# FMC_ADC_top.net
KiCad netlist of a schematic drawn in Altium Designer
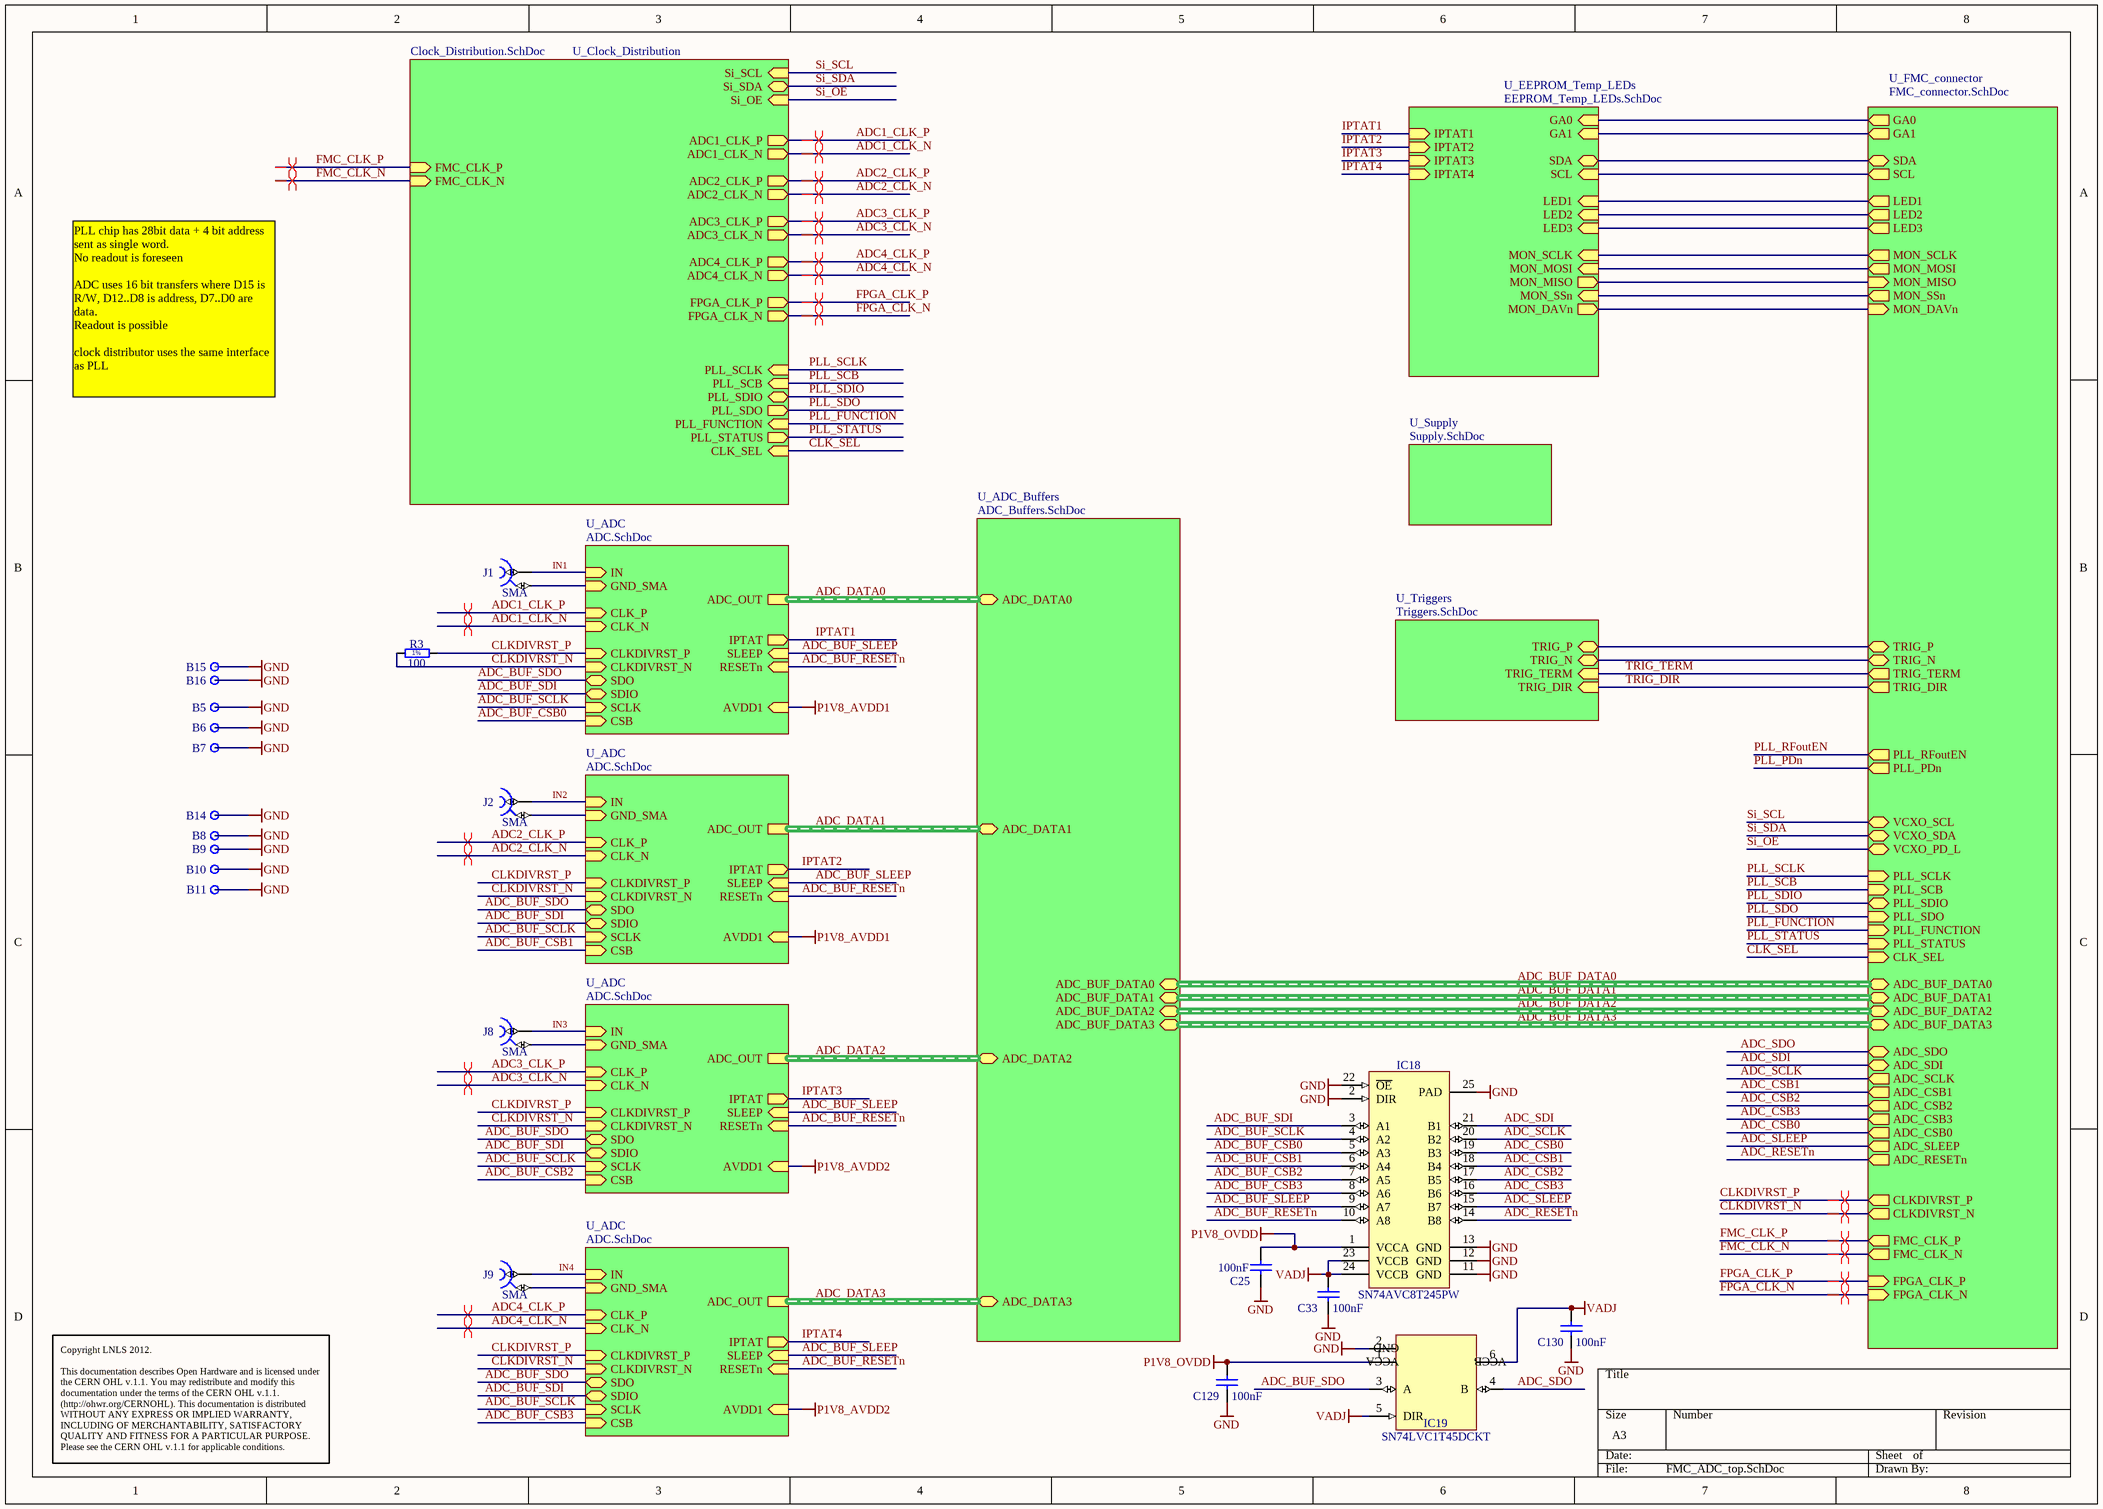
[diagram p0: FMC_ADC_top.SchDoc]

(export (version "E")
  (design (tool "Eeschema 10.0.6"))
  (components
    (comp (ref "B5")
      (value "Plated Hole")
      (footprint "MTG240_400_M")
      (description "Single Terminal Socket")
      (fields (field (name "PART NUMBER") "PLATED_HOLE2.4_PAD4.0_M") (field (name "AUTHOR") "LNLS DIG FCS"))
      (libsource (lib "Eletro-mechanical") (part "Single Terminal Socket"))
    )
    (comp (ref "B6")
      (value "Plated Hole")
      (footprint "MTG240_400_M")
      (description "Single Terminal Socket")
      (fields (field (name "PART NUMBER") "PLATED_HOLE2.4_PAD4.0_M") (field (name "AUTHOR") "LNLS DIG FCS"))
      (libsource (lib "Eletro-mechanical") (part "Single Terminal Socket"))
    )
    (comp (ref "B7")
      (value "Plated Hole")
      (footprint "MTG240_400_M")
      (description "Single Terminal Socket")
      (fields (field (name "PART NUMBER") "PLATED_HOLE2.4_PAD4.0_M") (field (name "AUTHOR") "LNLS DIG FCS"))
      (libsource (lib "Eletro-mechanical") (part "Single Terminal Socket"))
    )
    (comp (ref "B8")
      (value "Plated Hole")
      (footprint "MTG240_400_M")
      (description "Single Terminal Socket")
      (fields (field (name "PART NUMBER") "PLATED_HOLE2.4_PAD4.0_M") (field (name "AUTHOR") "LNLS DIG FCS"))
      (libsource (lib "Eletro-mechanical") (part "Single Terminal Socket"))
    )
    (comp (ref "B9")
      (value "Plated Hole")
      (footprint "MTG240_400_M")
      (description "Single Terminal Socket")
      (fields (field (name "PART NUMBER") "PLATED_HOLE2.4_PAD4.0_M") (field (name "AUTHOR") "LNLS DIG FCS"))
      (libsource (lib "Eletro-mechanical") (part "Single Terminal Socket"))
    )
    (comp (ref "B10")
      (value "Plated Hole")
      (footprint "MTG240_400_M")
      (description "Single Terminal Socket")
      (fields (field (name "PART NUMBER") "PLATED_HOLE2.4_PAD4.0_M") (field (name "AUTHOR") "LNLS DIG FCS"))
      (libsource (lib "Eletro-mechanical") (part "Single Terminal Socket"))
    )
    (comp (ref "B11")
      (value "Plated Hole")
      (footprint "MTG240_400_M")
      (description "Single Terminal Socket")
      (fields (field (name "PART NUMBER") "PLATED_HOLE2.4_PAD4.0_M") (field (name "AUTHOR") "LNLS DIG FCS"))
      (libsource (lib "Eletro-mechanical") (part "Single Terminal Socket"))
    )
    (comp (ref "B14")
      (value "Plated Hole")
      (footprint "MTG240_400_M")
      (description "Single Terminal Socket")
      (fields (field (name "PART NUMBER") "PLATED_HOLE2.4_PAD4.0_M") (field (name "AUTHOR") "LNLS DIG FCS"))
      (libsource (lib "Eletro-mechanical") (part "Single Terminal Socket"))
    )
    (comp (ref "B15")
      (value "Plated Hole")
      (footprint "MTG240_400_M")
      (description "Single Terminal Socket")
      (fields (field (name "PART NUMBER") "PLATED_HOLE2.4_PAD4.0_M") (field (name "AUTHOR") "LNLS DIG FCS"))
      (libsource (lib "Eletro-mechanical") (part "Single Terminal Socket"))
    )
    (comp (ref "B16")
      (value "Plated Hole")
      (footprint "MTG240_400_M")
      (description "Single Terminal Socket")
      (fields (field (name "PART NUMBER") "PLATED_HOLE2.4_PAD4.0_M") (field (name "AUTHOR") "LNLS DIG FCS"))
      (libsource (lib "Eletro-mechanical") (part "Single Terminal Socket"))
    )
    (comp (ref "C25")
      (value "100nF")
      (footprint "CAPC0603X33N")
      (description "Non-polarised capacitor")
      (fields
        (field (name "PART NUMBER") "CC0201_100NF_6.3V_10%_X5R")
        (field (name "VOLTAGE") "6.3V")
        (field (name "AUTHOR") "CERN DEM JLC")
      )
      (libsource (lib "Capacitors") (part "Capacitor - non polarized"))
    )
    (comp (ref "C33")
      (value "100nF")
      (footprint "CAPC0603X33N")
      (description "Non-polarised capacitor")
      (fields
        (field (name "PART NUMBER") "CC0201_100NF_6.3V_10%_X5R")
        (field (name "VOLTAGE") "6.3V")
        (field (name "AUTHOR") "CERN DEM JLC")
      )
      (libsource (lib "Capacitors") (part "Capacitor - non polarized"))
    )
    (comp (ref "C129")
      (value "100nF")
      (footprint "CAPC0603X33N")
      (description "Non-polarised capacitor")
      (fields
        (field (name "PART NUMBER") "CC0201_100NF_6.3V_10%_X5R")
        (field (name "VOLTAGE") "6.3V")
        (field (name "AUTHOR") "CERN DEM JLC")
      )
      (libsource (lib "Capacitors") (part "Capacitor - non polarized"))
    )
    (comp (ref "C130")
      (value "100nF")
      (footprint "CAPC0603X33N")
      (description "Non-polarised capacitor")
      (fields
        (field (name "PART NUMBER") "CC0201_100NF_6.3V_10%_X5R")
        (field (name "VOLTAGE") "6.3V")
        (field (name "AUTHOR") "CERN DEM JLC")
      )
      (libsource (lib "Capacitors") (part "Capacitor - non polarized"))
    )
    (comp (ref "IC18")
      (value "SN74AVC8T245PW")
      (footprint "SOP65P640X120-24N")
      (description "8-Bit Dual-Supply Bus Transceiver With Configurable Voltage Translation and 3-State Outputs")
      (fields (field (name "MANUFACTURER") "TEXAS INSTRUMENTS") (field (name "AUTHOR") "CERN DEM JLC"))
      (libsource (lib "ICs And Semiconductors") (part "748T245"))
    )
    (comp (ref "IC19")
      (value "SN74LVC1T45DCKT")
      (footprint "SOT65P210X110-6N")
      (description "Single-Bit Dual-Supply Bus Transceiver")
      (fields (field (name "MANUFACTURER") "TEXAS INSTRUMENTS") (field (name "AUTHOR") "CERN DEM JLC"))
      (libsource (lib "ICs And Semiconductors") (part "741T45"))
    )
    (comp (ref "J1")
      (value "SMA")
      (footprint "AMPHENOL_901-143_IN BOARD")
      (fields
        (field (name "PART NUMBER") "AMPHENOL_901-143-6RFX")
        (field (name "MANUFACTURER") "AMPHENOL")
        (field (name "MANUFACTURER PART NUMBER") "901-143-6RFX")
        (field (name "AUTHOR") "LNLS DIG GBMB")
      )
      (libsource (lib "Connectors") (part "Coax_1Female_1Shield"))
    )
    (comp (ref "J2")
      (value "SMA")
      (footprint "AMPHENOL_901-143_IN BOARD")
      (fields
        (field (name "PART NUMBER") "AMPHENOL_901-143-6RFX")
        (field (name "MANUFACTURER") "AMPHENOL")
        (field (name "MANUFACTURER PART NUMBER") "901-143-6RFX")
        (field (name "AUTHOR") "LNLS DIG GBMB")
      )
      (libsource (lib "Connectors") (part "Coax_1Female_1Shield"))
    )
    (comp (ref "J8")
      (value "SMA")
      (footprint "AMPHENOL_901-143_IN BOARD")
      (fields
        (field (name "PART NUMBER") "AMPHENOL_901-143-6RFX")
        (field (name "MANUFACTURER") "AMPHENOL")
        (field (name "MANUFACTURER PART NUMBER") "901-143-6RFX")
        (field (name "AUTHOR") "LNLS DIG GBMB")
      )
      (libsource (lib "Connectors") (part "Coax_1Female_1Shield"))
    )
    (comp (ref "J9")
      (value "SMA")
      (footprint "AMPHENOL_901-143_IN BOARD")
      (fields
        (field (name "PART NUMBER") "AMPHENOL_901-143-6RFX")
        (field (name "MANUFACTURER") "AMPHENOL")
        (field (name "MANUFACTURER PART NUMBER") "901-143-6RFX")
        (field (name "AUTHOR") "LNLS DIG GBMB")
      )
      (libsource (lib "Connectors") (part "Coax_1Female_1Shield"))
    )
    (comp (ref "R3")
      (value "100")
      (footprint "RESC1005X40N")
      (description "Resistor - 1%")
      (fields
        (field (name "PART NUMBER") "R0402_100R_1%_0.0625W_100PPM")
        (field (name "POWER") "0.0625W")
        (field (name "AUTHOR") "CERN DEM JLC")
      )
      (libsource (lib "Resistors") (part "Resistor - 1%"))
    )
  )
  (nets
    (net (code "17") (name "/ADC_BUF_CSB0") (class "Default")
      (node (ref "IC18") (pin "5") (pinfunction "A3_5") (pintype "bidirectional"))
    )
    (net (code "18") (name "/ADC_BUF_CSB1") (class "Default")
      (node (ref "IC18") (pin "6") (pinfunction "A4_6") (pintype "bidirectional"))
    )
    (net (code "19") (name "/ADC_BUF_CSB2") (class "Default")
      (node (ref "IC18") (pin "7") (pinfunction "A5_7") (pintype "bidirectional"))
    )
    (net (code "20") (name "/ADC_BUF_CSB3") (class "Default")
      (node (ref "IC18") (pin "8") (pinfunction "A6_8") (pintype "bidirectional"))
    )
    (net (code "21") (name "/ADC_BUF_RESETn") (class "Default")
      (node (ref "IC18") (pin "10") (pinfunction "A8_10") (pintype "bidirectional"))
    )
    (net (code "22") (name "/ADC_BUF_SCLK") (class "Default")
      (node (ref "IC18") (pin "4") (pinfunction "A2_4") (pintype "bidirectional"))
    )
    (net (code "23") (name "/ADC_BUF_SDI") (class "Default")
      (node (ref "IC18") (pin "3") (pinfunction "A1_3") (pintype "bidirectional"))
    )
    (net (code "24") (name "/ADC_BUF_SDO") (class "Default")
      (node (ref "IC19") (pin "3") (pinfunction "A_3") (pintype "bidirectional"))
    )
    (net (code "25") (name "/ADC_BUF_SLEEP") (class "Default")
      (node (ref "IC18") (pin "9") (pinfunction "A7_9") (pintype "bidirectional"))
    )
    (net (code "26") (name "/ADC_CSB0") (class "Default")
      (node (ref "IC18") (pin "19") (pinfunction "B3_19") (pintype "bidirectional"))
    )
    (net (code "27") (name "/ADC_CSB1") (class "Default")
      (node (ref "IC18") (pin "18") (pinfunction "B4_18") (pintype "bidirectional"))
    )
    (net (code "28") (name "/ADC_CSB2") (class "Default")
      (node (ref "IC18") (pin "17") (pinfunction "B5_17") (pintype "bidirectional"))
    )
    (net (code "29") (name "/ADC_CSB3") (class "Default")
      (node (ref "IC18") (pin "16") (pinfunction "B6_16") (pintype "bidirectional"))
    )
    (net (code "30") (name "/ADC_RESETn") (class "Default")
      (node (ref "IC18") (pin "14") (pinfunction "B8_14") (pintype "bidirectional"))
    )
    (net (code "31") (name "/ADC_SCLK") (class "Default")
      (node (ref "IC18") (pin "20") (pinfunction "B2_20") (pintype "bidirectional"))
    )
    (net (code "32") (name "/ADC_SDI") (class "Default")
      (node (ref "IC18") (pin "21") (pinfunction "B1_21") (pintype "bidirectional"))
    )
    (net (code "33") (name "/ADC_SDO") (class "Default")
      (node (ref "IC19") (pin "4") (pinfunction "B_4") (pintype "bidirectional"))
    )
    (net (code "34") (name "/ADC_SLEEP") (class "Default")
      (node (ref "IC18") (pin "15") (pinfunction "B7_15") (pintype "bidirectional"))
    )
    (net (code "35") (name "/CLKDIVRST_N") (class "Default")
      (node (ref "R3") (pin "1") (pinfunction "1_1") (pintype "passive"))
    )
    (net (code "36") (name "/CLKDIVRST_P") (class "Default")
      (node (ref "R3") (pin "2") (pinfunction "2_2") (pintype "passive"))
    )
    (net (code "44") (name "/GND_SMA") (class "Default")
      (node (ref "J9") (pin "2") (pinfunction "2_2") (pintype "bidirectional"))
    )
    (net (code "45") (name "/GND_SMA_1") (class "Default")
      (node (ref "J2") (pin "2") (pinfunction "2_2") (pintype "bidirectional"))
    )
    (net (code "46") (name "/GND_SMA_2") (class "Default")
      (node (ref "J1") (pin "2") (pinfunction "2_2") (pintype "bidirectional"))
    )
    (net (code "47") (name "/GND_SMA_3") (class "Default")
      (node (ref "J8") (pin "2") (pinfunction "2_2") (pintype "bidirectional"))
    )
    (net (code "48") (name "/IN1") (class "Default")
      (node (ref "J1") (pin "1") (pinfunction "1_1") (pintype "bidirectional"))
    )
    (net (code "49") (name "/IN2") (class "Default")
      (node (ref "J2") (pin "1") (pinfunction "1_1") (pintype "bidirectional"))
    )
    (net (code "50") (name "/IN3") (class "Default")
      (node (ref "J8") (pin "1") (pinfunction "1_1") (pintype "bidirectional"))
    )
    (net (code "51") (name "/IN4") (class "Default")
      (node (ref "J9") (pin "1") (pinfunction "1_1") (pintype "bidirectional"))
    )
    (net (code "89") (name "GND") (class "Default")
      (node (ref "B10") (pin "1") (pinfunction "1_1") (pintype "bidirectional"))
      (node (ref "B11") (pin "1") (pinfunction "1_1") (pintype "bidirectional"))
      (node (ref "B14") (pin "1") (pinfunction "1_1") (pintype "bidirectional"))
      (node (ref "B15") (pin "1") (pinfunction "1_1") (pintype "bidirectional"))
      (node (ref "B16") (pin "1") (pinfunction "1_1") (pintype "bidirectional"))
      (node (ref "B5") (pin "1") (pinfunction "1_1") (pintype "bidirectional"))
      (node (ref "B6") (pin "1") (pinfunction "1_1") (pintype "bidirectional"))
      (node (ref "B7") (pin "1") (pinfunction "1_1") (pintype "bidirectional"))
      (node (ref "B8") (pin "1") (pinfunction "1_1") (pintype "bidirectional"))
      (node (ref "B9") (pin "1") (pinfunction "1_1") (pintype "bidirectional"))
      (node (ref "C129") (pin "1") (pinfunction "1_1") (pintype "passive"))
      (node (ref "C130") (pin "1") (pinfunction "1_1") (pintype "passive"))
      (node (ref "C25") (pin "2") (pinfunction "2_2") (pintype "passive"))
      (node (ref "C33") (pin "1") (pinfunction "1_1") (pintype "passive"))
      (node (ref "IC18") (pin "11") (pinfunction "GND_11") (pintype "power_in"))
      (node (ref "IC18") (pin "12") (pinfunction "GND_12") (pintype "power_in"))
      (node (ref "IC18") (pin "13") (pinfunction "GND_13") (pintype "power_in"))
      (node (ref "IC18") (pin "2") (pinfunction "DIR_2") (pintype "input"))
      (node (ref "IC18") (pin "22") (pinfunction "~{OE}_22") (pintype "input"))
      (node (ref "IC18") (pin "25") (pinfunction "PAD_25") (pintype "power_in"))
      (node (ref "IC19") (pin "2") (pinfunction "GND_2") (pintype "power_in"))
    )
    (net (code "92") (name "P1V8_OVDD") (class "Default")
      (node (ref "C129") (pin "2") (pinfunction "2_2") (pintype "passive"))
      (node (ref "C25") (pin "1") (pinfunction "1_1") (pintype "passive"))
      (node (ref "IC18") (pin "1") (pinfunction "VCCA_1") (pintype "power_in"))
      (node (ref "IC19") (pin "1") (pinfunction "VCCA_1") (pintype "power_in"))
    )
    (net (code "93") (name "VADJ") (class "Default")
      (node (ref "C130") (pin "2") (pinfunction "2_2") (pintype "passive"))
      (node (ref "C33") (pin "2") (pinfunction "2_2") (pintype "passive"))
      (node (ref "IC18") (pin "23") (pinfunction "VCCB_23") (pintype "power_in"))
      (node (ref "IC18") (pin "24") (pinfunction "VCCB_24") (pintype "power_in"))
      (node (ref "IC19") (pin "5") (pinfunction "DIR_5") (pintype "input"))
      (node (ref "IC19") (pin "6") (pinfunction "VCCB_6") (pintype "power_in"))
    )
  )
)
